# MCU.net
KiCad netlist of a schematic drawn in Altium Designer
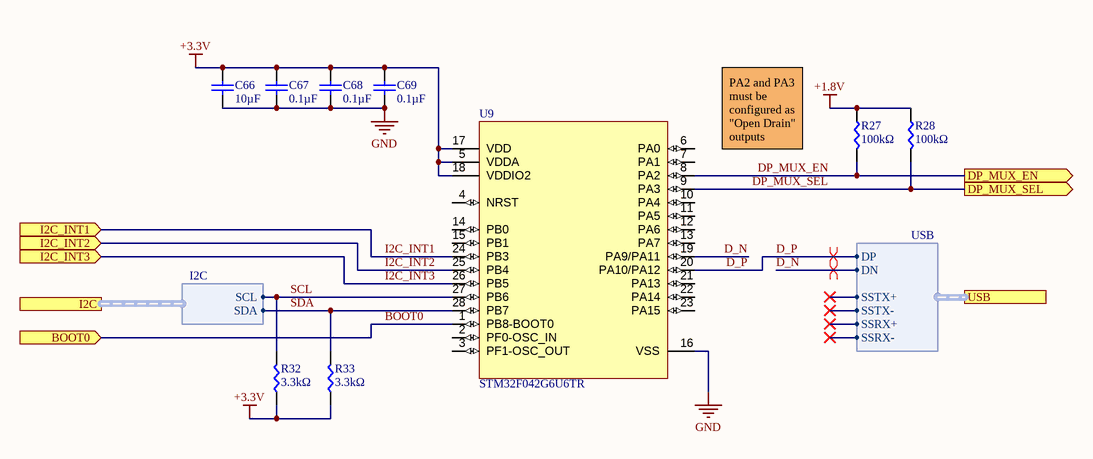
[diagram p0: MCU.SchDoc]

(export (version "E")
  (design (tool "Eeschema 10.0.6"))
  (components
    (comp (ref "C66")
      (value "10µF")
      (footprint "CAP0402")
      (description "10 µF ±20% 6.3V Ceramic Capacitor X5R 0402 (1005 Metric)")
      (fields (field (name "VOLTAGE") "6.3V") (field (name "Comment") "CL05A106MQ5NUNC"))
      (libsource (lib "Schlib1") (part "CL05A106MQ5NUNC"))
    )
    (comp (ref "C67")
      (value "0.1µF")
      (footprint "CAP0402")
      (description "0.1 µF ±10% 50V Ceramic Capacitor X5R 0402 (1005 Metric)")
      (fields (field (name "VOLTAGE") "50V") (field (name "Comment") "CC0402KRX5R9BB104"))
      (libsource (lib "Schlib1") (part "CC0402KRX5R9BB104"))
    )
    (comp (ref "C68")
      (value "0.1µF")
      (footprint "CAP0402")
      (description "0.1 µF ±10% 50V Ceramic Capacitor X5R 0402 (1005 Metric)")
      (fields (field (name "VOLTAGE") "50V") (field (name "Comment") "CC0402KRX5R9BB104"))
      (libsource (lib "Schlib1") (part "CC0402KRX5R9BB104"))
    )
    (comp (ref "C69")
      (value "0.1µF")
      (footprint "CAP0402")
      (description "0.1 µF ±10% 50V Ceramic Capacitor X5R 0402 (1005 Metric)")
      (fields (field (name "VOLTAGE") "50V") (field (name "Comment") "CC0402KRX5R9BB104"))
      (libsource (lib "Schlib1") (part "CC0402KRX5R9BB104"))
    )
    (comp (ref "R27")
      (value "100kΩ")
      (footprint "RES0402")
      (description "100 kOhms ±1% 0.1W, 1/10W Chip Resistor 0402 (1005 Metric) Automotive AEC-Q200 Thick Film")
      (fields (field (name "Comment") "ERJ-2RKF1003X"))
      (libsource (lib "Schlib1") (part "ERJ-2RKF1003X"))
    )
    (comp (ref "R28")
      (value "100kΩ")
      (footprint "RES0402")
      (description "100 kOhms ±1% 0.1W, 1/10W Chip Resistor 0402 (1005 Metric) Automotive AEC-Q200 Thick Film")
      (fields (field (name "Comment") "ERJ-2RKF1003X"))
      (libsource (lib "Schlib1") (part "ERJ-2RKF1003X"))
    )
    (comp (ref "R32")
      (value "3.3kΩ")
      (footprint "RES0402")
      (description "3.3 kOhms ±0.1% 0.063W, 1/16W Chip Resistor 0402 (1005 Metric) Automotive AEC-Q200 Thin Film")
      (fields (field (name "Comment") "ERA-2AEB332X"))
      (libsource (lib "Schlib1") (part "ERA-2AEB332X"))
    )
    (comp (ref "R33")
      (value "3.3kΩ")
      (footprint "RES0402")
      (description "3.3 kOhms ±0.1% 0.063W, 1/16W Chip Resistor 0402 (1005 Metric) Automotive AEC-Q200 Thin Film")
      (fields (field (name "Comment") "ERA-2AEB332X"))
      (libsource (lib "Schlib1") (part "ERA-2AEB332X"))
    )
    (comp (ref "U9")
      (value "STM32F042G6U6TR")
      (footprint "UFQFPN28-4x4mm")
      (fields (field (name "COPYRIGHT") "Copyright (C) 2026 Ultra Librarian. All rights reserved."))
      (libsource (lib "Schlib1") (part "STM32F042G6U6TR"))
    )
  )
  (nets
    (net (code "3") (name "+1.8V") (class "Default")
      (node (ref "R27") (pin "2") (pinfunction "2_2") (pintype "passive"))
      (node (ref "R28") (pin "2") (pinfunction "2_2") (pintype "passive"))
    )
    (net (code "4") (name "+3.3V") (class "Default")
      (node (ref "C66") (pin "2") (pinfunction "2_2") (pintype "passive"))
      (node (ref "C67") (pin "2") (pinfunction "2_2") (pintype "passive"))
      (node (ref "C68") (pin "2") (pinfunction "2_2") (pintype "passive"))
      (node (ref "C69") (pin "2") (pinfunction "2_2") (pintype "passive"))
      (node (ref "R32") (pin "2") (pinfunction "2_2") (pintype "passive"))
      (node (ref "R33") (pin "2") (pinfunction "2_2") (pintype "passive"))
      (node (ref "U9") (pin "17") (pinfunction "VDD_17") (pintype "power_in"))
      (node (ref "U9") (pin "18") (pinfunction "VDDIO2_18") (pintype "power_in"))
      (node (ref "U9") (pin "5") (pinfunction "VDDA_5") (pintype "power_in"))
    )
    (net (code "5") (name "/BOOT0") (class "Default")
      (node (ref "U9") (pin "1") (pinfunction "PB8-BOOT0_1") (pintype "bidirectional"))
    )
    (net (code "6") (name "/DP_MUX_EN") (class "Default")
      (node (ref "R27") (pin "1") (pinfunction "1_1") (pintype "passive"))
      (node (ref "U9") (pin "8") (pinfunction "PA2_8") (pintype "bidirectional"))
    )
    (net (code "7") (name "/DP_MUX_SEL") (class "Default")
      (node (ref "R28") (pin "1") (pinfunction "1_1") (pintype "passive"))
      (node (ref "U9") (pin "9") (pinfunction "PA3_9") (pintype "bidirectional"))
    )
    (net (code "8") (name "/D_N") (class "Default")
      (node (ref "U9") (pin "19") (pinfunction "PA9/PA11_19") (pintype "bidirectional"))
    )
    (net (code "9") (name "/D_P") (class "Default")
      (node (ref "U9") (pin "20") (pinfunction "PA10/PA12_20") (pintype "bidirectional"))
    )
    (net (code "10") (name "/I2C_INT1") (class "Default")
      (node (ref "U9") (pin "24") (pinfunction "PB3_24") (pintype "bidirectional"))
    )
    (net (code "11") (name "/I2C_INT2") (class "Default")
      (node (ref "U9") (pin "25") (pinfunction "PB4_25") (pintype "bidirectional"))
    )
    (net (code "12") (name "/I2C_INT3") (class "Default")
      (node (ref "U9") (pin "26") (pinfunction "PB5_26") (pintype "bidirectional"))
    )
    (net (code "13") (name "/SCL") (class "Default")
      (node (ref "R32") (pin "1") (pinfunction "1_1") (pintype "passive"))
      (node (ref "U9") (pin "27") (pinfunction "PB6_27") (pintype "bidirectional"))
    )
    (net (code "14") (name "/SDA") (class "Default")
      (node (ref "R33") (pin "1") (pinfunction "1_1") (pintype "passive"))
      (node (ref "U9") (pin "28") (pinfunction "PB7_28") (pintype "bidirectional"))
    )
    (net (code "17") (name "GND") (class "Default")
      (node (ref "C66") (pin "1") (pinfunction "1_1") (pintype "passive"))
      (node (ref "C67") (pin "1") (pinfunction "1_1") (pintype "passive"))
      (node (ref "C68") (pin "1") (pinfunction "1_1") (pintype "passive"))
      (node (ref "C69") (pin "1") (pinfunction "1_1") (pintype "passive"))
      (node (ref "U9") (pin "16") (pinfunction "VSS_16") (pintype "power_in"))
    )
    (net (code "18") (name "unconnected-(U9-NRST-Pad4)") (class "Default")
      (node (ref "U9") (pin "4") (pinfunction "NRST_4") (pintype "bidirectional"))
    )
    (net (code "19") (name "unconnected-(U9-PA0-Pad6)") (class "Default")
      (node (ref "U9") (pin "6") (pinfunction "PA0_6") (pintype "bidirectional"))
    )
    (net (code "20") (name "unconnected-(U9-PA1-Pad7)") (class "Default")
      (node (ref "U9") (pin "7") (pinfunction "PA1_7") (pintype "bidirectional"))
    )
    (net (code "21") (name "unconnected-(U9-PA4-Pad10)") (class "Default")
      (node (ref "U9") (pin "10") (pinfunction "PA4_10") (pintype "bidirectional"))
    )
    (net (code "22") (name "unconnected-(U9-PA5-Pad11)") (class "Default")
      (node (ref "U9") (pin "11") (pinfunction "PA5_11") (pintype "bidirectional"))
    )
    (net (code "23") (name "unconnected-(U9-PA6-Pad12)") (class "Default")
      (node (ref "U9") (pin "12") (pinfunction "PA6_12") (pintype "bidirectional"))
    )
    (net (code "24") (name "unconnected-(U9-PA7-Pad13)") (class "Default")
      (node (ref "U9") (pin "13") (pinfunction "PA7_13") (pintype "bidirectional"))
    )
    (net (code "25") (name "unconnected-(U9-PA13-Pad21)") (class "Default")
      (node (ref "U9") (pin "21") (pinfunction "PA13_21") (pintype "bidirectional"))
    )
    (net (code "26") (name "unconnected-(U9-PA14-Pad22)") (class "Default")
      (node (ref "U9") (pin "22") (pinfunction "PA14_22") (pintype "bidirectional"))
    )
    (net (code "27") (name "unconnected-(U9-PA15-Pad23)") (class "Default")
      (node (ref "U9") (pin "23") (pinfunction "PA15_23") (pintype "bidirectional"))
    )
    (net (code "28") (name "unconnected-(U9-PB0-Pad14)") (class "Default")
      (node (ref "U9") (pin "14") (pinfunction "PB0_14") (pintype "bidirectional"))
    )
    (net (code "29") (name "unconnected-(U9-PB1-Pad15)") (class "Default")
      (node (ref "U9") (pin "15") (pinfunction "PB1_15") (pintype "bidirectional"))
    )
    (net (code "30") (name "unconnected-(U9-PF0-OSC_IN-Pad2)") (class "Default")
      (node (ref "U9") (pin "2") (pinfunction "PF0-OSC_IN_2") (pintype "bidirectional"))
    )
    (net (code "31") (name "unconnected-(U9-PF1-OSC_OUT-Pad3)") (class "Default")
      (node (ref "U9") (pin "3") (pinfunction "PF1-OSC_OUT_3") (pintype "bidirectional"))
    )
  )
)
